# mx_9_3s.net
KiCad netlist of a schematic drawn in EAGLE
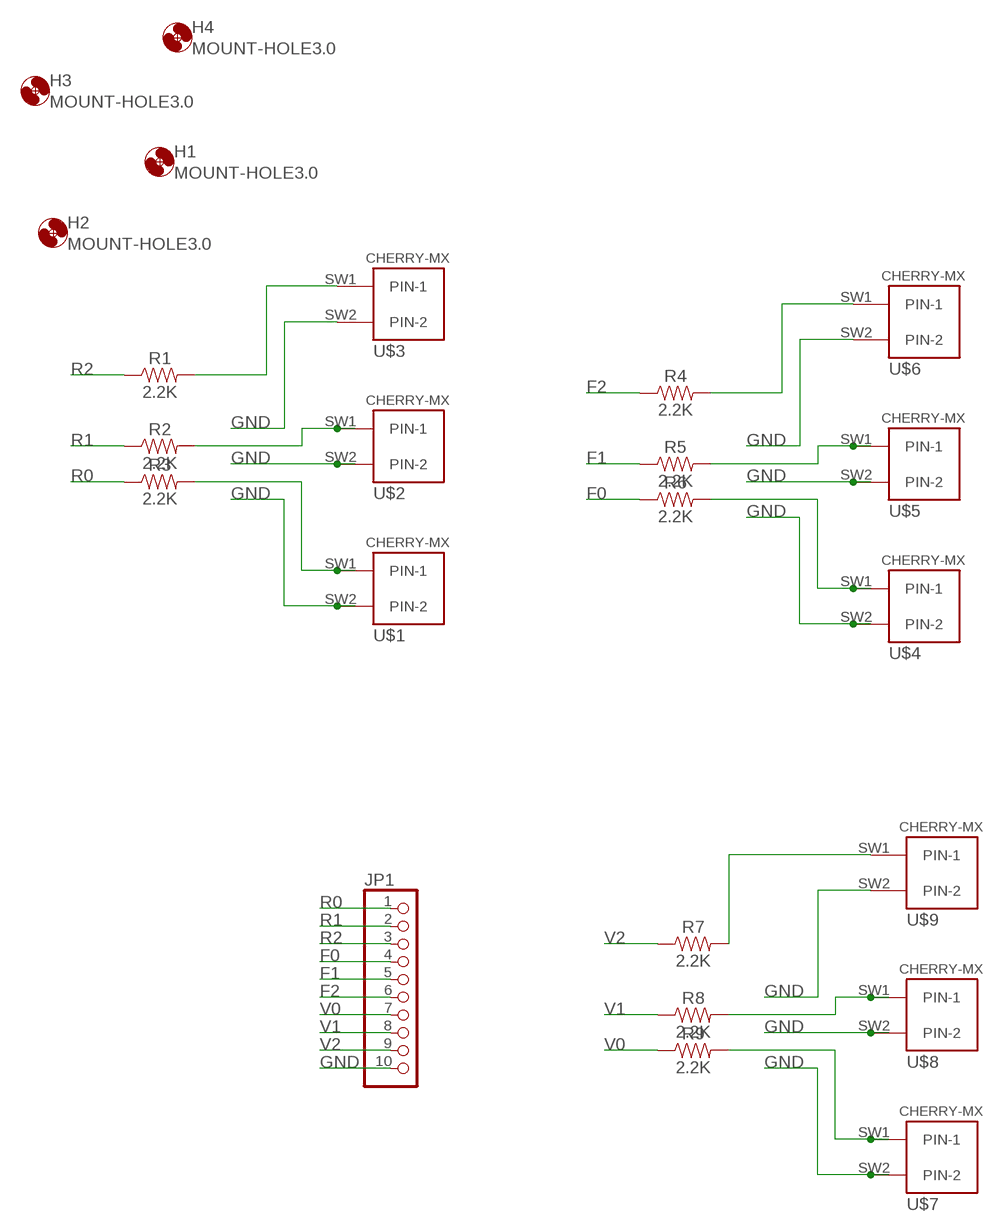
[diagram p0: schematic, sheet 1]

(export (version "E")
  (design (tool "Eeschema 10.0.6"))
  (components
    (comp (ref "H1")
      (value "MOUNT-HOLE3.0")
      (footprint "eagle-import:3,0")
      (libsource (lib "eagle-import") (part "MOUNT-HOLE3.0"))
    )
    (comp (ref "H2")
      (value "MOUNT-HOLE3.0")
      (footprint "eagle-import:3,0")
      (libsource (lib "eagle-import") (part "MOUNT-HOLE3.0"))
    )
    (comp (ref "H3")
      (value "MOUNT-HOLE3.0")
      (footprint "eagle-import:3,0")
      (libsource (lib "eagle-import") (part "MOUNT-HOLE3.0"))
    )
    (comp (ref "H4")
      (value "MOUNT-HOLE3.0")
      (footprint "eagle-import:3,0")
      (libsource (lib "eagle-import") (part "MOUNT-HOLE3.0"))
    )
    (comp (ref "JP1")
      (value "PINHD-1X10")
      (footprint "eagle-import:1X10")
      (libsource (lib "eagle-import") (part "PINHD-1X10"))
    )
    (comp (ref "R1")
      (value "2.2K")
      (footprint "eagle-import:0402")
      (libsource (lib "eagle-import") (part "2.2KOHM-0402-1/16W-1%"))
    )
    (comp (ref "R2")
      (value "2.2K")
      (footprint "eagle-import:0402")
      (libsource (lib "eagle-import") (part "2.2KOHM-0402-1/16W-1%"))
    )
    (comp (ref "R3")
      (value "2.2K")
      (footprint "eagle-import:0402")
      (libsource (lib "eagle-import") (part "2.2KOHM-0402-1/16W-1%"))
    )
    (comp (ref "R4")
      (value "2.2K")
      (footprint "eagle-import:0402")
      (libsource (lib "eagle-import") (part "2.2KOHM-0402-1/16W-1%"))
    )
    (comp (ref "R5")
      (value "2.2K")
      (footprint "eagle-import:0402")
      (libsource (lib "eagle-import") (part "2.2KOHM-0402-1/16W-1%"))
    )
    (comp (ref "R6")
      (value "2.2K")
      (footprint "eagle-import:0402")
      (libsource (lib "eagle-import") (part "2.2KOHM-0402-1/16W-1%"))
    )
    (comp (ref "R7")
      (value "2.2K")
      (footprint "eagle-import:0402")
      (libsource (lib "eagle-import") (part "2.2KOHM-0402-1/16W-1%"))
    )
    (comp (ref "R8")
      (value "2.2K")
      (footprint "eagle-import:0402")
      (libsource (lib "eagle-import") (part "2.2KOHM-0402-1/16W-1%"))
    )
    (comp (ref "R9")
      (value "2.2K")
      (footprint "eagle-import:0402")
      (libsource (lib "eagle-import") (part "2.2KOHM-0402-1/16W-1%"))
    )
    (comp (ref "U$1")
      (value "CHERRY-MX")
      (footprint "eagle-import:CHERRY-MX")
      (libsource (lib "eagle-import") (part "CHERRY-MX"))
    )
    (comp (ref "U$2")
      (value "CHERRY-MX")
      (footprint "eagle-import:CHERRY-MX")
      (libsource (lib "eagle-import") (part "CHERRY-MX"))
    )
    (comp (ref "U$3")
      (value "CHERRY-MX")
      (footprint "eagle-import:CHERRY-MX")
      (libsource (lib "eagle-import") (part "CHERRY-MX"))
    )
    (comp (ref "U$4")
      (value "CHERRY-MX")
      (footprint "eagle-import:CHERRY-MX")
      (libsource (lib "eagle-import") (part "CHERRY-MX"))
    )
    (comp (ref "U$5")
      (value "CHERRY-MX")
      (footprint "eagle-import:CHERRY-MX")
      (libsource (lib "eagle-import") (part "CHERRY-MX"))
    )
    (comp (ref "U$6")
      (value "CHERRY-MX")
      (footprint "eagle-import:CHERRY-MX")
      (libsource (lib "eagle-import") (part "CHERRY-MX"))
    )
    (comp (ref "U$7")
      (value "CHERRY-MX")
      (footprint "eagle-import:CHERRY-MX")
      (libsource (lib "eagle-import") (part "CHERRY-MX"))
    )
    (comp (ref "U$8")
      (value "CHERRY-MX")
      (footprint "eagle-import:CHERRY-MX")
      (libsource (lib "eagle-import") (part "CHERRY-MX"))
    )
    (comp (ref "U$9")
      (value "CHERRY-MX")
      (footprint "eagle-import:CHERRY-MX")
      (libsource (lib "eagle-import") (part "CHERRY-MX"))
    )
  )
  (nets
    (net (code "1") (name "/F0") (class "Default")
      (node (ref "JP1") (pin "4") (pinfunction "4_4") (pintype "passive"))
      (node (ref "R6") (pin "1") (pinfunction "1_1") (pintype "passive"))
    )
    (net (code "2") (name "/F1") (class "Default")
      (node (ref "JP1") (pin "5") (pinfunction "5_5") (pintype "passive"))
      (node (ref "R5") (pin "1") (pinfunction "1_1") (pintype "passive"))
    )
    (net (code "3") (name "/F2") (class "Default")
      (node (ref "JP1") (pin "6") (pinfunction "6_6") (pintype "passive"))
      (node (ref "R4") (pin "1") (pinfunction "1_1") (pintype "passive"))
    )
    (net (code "4") (name "/GND") (class "Default")
      (node (ref "JP1") (pin "10") (pinfunction "10_10") (pintype "passive"))
      (node (ref "U$1") (pin "SW2") (pinfunction "PIN-2_SW2") (pintype "bidirectional"))
      (node (ref "U$2") (pin "SW2") (pinfunction "PIN-2_SW2") (pintype "bidirectional"))
      (node (ref "U$3") (pin "SW2") (pinfunction "PIN-2_SW2") (pintype "bidirectional"))
      (node (ref "U$4") (pin "SW2") (pinfunction "PIN-2_SW2") (pintype "bidirectional"))
      (node (ref "U$5") (pin "SW2") (pinfunction "PIN-2_SW2") (pintype "bidirectional"))
      (node (ref "U$6") (pin "SW2") (pinfunction "PIN-2_SW2") (pintype "bidirectional"))
      (node (ref "U$7") (pin "SW2") (pinfunction "PIN-2_SW2") (pintype "bidirectional"))
      (node (ref "U$8") (pin "SW2") (pinfunction "PIN-2_SW2") (pintype "bidirectional"))
      (node (ref "U$9") (pin "SW2") (pinfunction "PIN-2_SW2") (pintype "bidirectional"))
    )
    (net (code "5") (name "/R0") (class "Default")
      (node (ref "JP1") (pin "1") (pinfunction "1_1") (pintype "passive"))
      (node (ref "R3") (pin "1") (pinfunction "1_1") (pintype "passive"))
    )
    (net (code "6") (name "/R1") (class "Default")
      (node (ref "JP1") (pin "2") (pinfunction "2_2") (pintype "passive"))
      (node (ref "R2") (pin "1") (pinfunction "1_1") (pintype "passive"))
    )
    (net (code "7") (name "/R2") (class "Default")
      (node (ref "JP1") (pin "3") (pinfunction "3_3") (pintype "passive"))
      (node (ref "R1") (pin "1") (pinfunction "1_1") (pintype "passive"))
    )
    (net (code "8") (name "/V0") (class "Default")
      (node (ref "JP1") (pin "7") (pinfunction "7_7") (pintype "passive"))
      (node (ref "R9") (pin "1") (pinfunction "1_1") (pintype "passive"))
    )
    (net (code "9") (name "/V1") (class "Default")
      (node (ref "JP1") (pin "8") (pinfunction "8_8") (pintype "passive"))
      (node (ref "R8") (pin "1") (pinfunction "1_1") (pintype "passive"))
    )
    (net (code "10") (name "/V2") (class "Default")
      (node (ref "JP1") (pin "9") (pinfunction "9_9") (pintype "passive"))
      (node (ref "R7") (pin "1") (pinfunction "1_1") (pintype "passive"))
    )
    (net (code "11") (name "Net-(U$1-PIN-1)") (class "Default")
      (node (ref "R3") (pin "2") (pinfunction "2_2") (pintype "passive"))
      (node (ref "U$1") (pin "SW1") (pinfunction "PIN-1_SW1") (pintype "bidirectional"))
    )
    (net (code "12") (name "Net-(U$2-PIN-1)") (class "Default")
      (node (ref "R2") (pin "2") (pinfunction "2_2") (pintype "passive"))
      (node (ref "U$2") (pin "SW1") (pinfunction "PIN-1_SW1") (pintype "bidirectional"))
    )
    (net (code "13") (name "Net-(U$3-PIN-1)") (class "Default")
      (node (ref "R1") (pin "2") (pinfunction "2_2") (pintype "passive"))
      (node (ref "U$3") (pin "SW1") (pinfunction "PIN-1_SW1") (pintype "bidirectional"))
    )
    (net (code "14") (name "Net-(U$4-PIN-1)") (class "Default")
      (node (ref "R6") (pin "2") (pinfunction "2_2") (pintype "passive"))
      (node (ref "U$4") (pin "SW1") (pinfunction "PIN-1_SW1") (pintype "bidirectional"))
    )
    (net (code "15") (name "Net-(U$5-PIN-1)") (class "Default")
      (node (ref "R5") (pin "2") (pinfunction "2_2") (pintype "passive"))
      (node (ref "U$5") (pin "SW1") (pinfunction "PIN-1_SW1") (pintype "bidirectional"))
    )
    (net (code "16") (name "Net-(U$6-PIN-1)") (class "Default")
      (node (ref "R4") (pin "2") (pinfunction "2_2") (pintype "passive"))
      (node (ref "U$6") (pin "SW1") (pinfunction "PIN-1_SW1") (pintype "bidirectional"))
    )
    (net (code "17") (name "Net-(U$7-PIN-1)") (class "Default")
      (node (ref "R9") (pin "2") (pinfunction "2_2") (pintype "passive"))
      (node (ref "U$7") (pin "SW1") (pinfunction "PIN-1_SW1") (pintype "bidirectional"))
    )
    (net (code "18") (name "Net-(U$8-PIN-1)") (class "Default")
      (node (ref "R8") (pin "2") (pinfunction "2_2") (pintype "passive"))
      (node (ref "U$8") (pin "SW1") (pinfunction "PIN-1_SW1") (pintype "bidirectional"))
    )
    (net (code "19") (name "Net-(U$9-PIN-1)") (class "Default")
      (node (ref "R7") (pin "2") (pinfunction "2_2") (pintype "passive"))
      (node (ref "U$9") (pin "SW1") (pinfunction "PIN-1_SW1") (pintype "bidirectional"))
    )
  )
)
